# rev1.net
KiCad netlist of a schematic drawn in Altium Designer
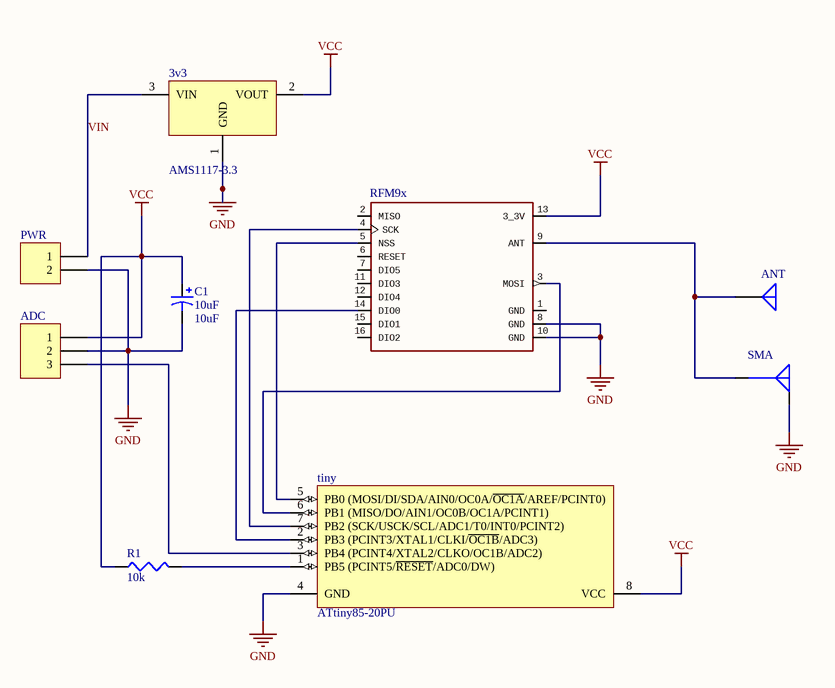
[diagram p0: rev1.SchDoc]

(export (version "E")
  (design (tool "Eeschema 10.0.6"))
  (components
    (comp (ref "3v3")
      (value "AMS1117-3.3")
      (footprint "SOT-223")
      (description "3.3V  3-Terminal Adjustable Positive Voltage Regulator")
      (libsource (lib "Analog IC") (part "AMS1117-3.3"))
    )
    (comp (ref "ADC")
      (value "~")
      (footprint "HDR1X3")
      (description "Header, 3-Pin")
      (fields (field (name "PUBLISHER") "Altium Limited"))
      (libsource (lib "Miscellaneous Connectors") (part "Header 3"))
    )
    (comp (ref "ANT")
      (value "~")
      (footprint "PIN1")
      (description "Generic Antenna")
      (fields (field (name "PUBLISHER") "Altium Limited"))
      (libsource (lib "Miscellaneous Devices") (part "Antenna"))
    )
    (comp (ref "C1")
      (value "10uF")
      (footprint "C0805")
      (description "Polarized Capacitor (Surface Mount)")
      (fields (field (name "ALTIUM_VALUE") "10uF") (field (name "PUBLISHER") "Altium Limited"))
      (libsource (lib "LoRa_v1") (part "Cap Pol3"))
    )
    (comp (ref "PWR")
      (value "~")
      (footprint "HDR1X2")
      (description "Header, 2-Pin")
      (fields (field (name "PUBLISHER") "Altium Limited"))
      (libsource (lib "Miscellaneous Connectors") (part "Header 2"))
    )
    (comp (ref "R1")
      (value "10k")
      (footprint "C0805")
      (description "Resistor")
      (fields (field (name "PUBLISHER") "Altium Limited"))
      (libsource (lib "LoRa_v1") (part "Res3"))
    )
    (comp (ref "RFM9x")
      (value "~")
      (footprint "XCVR_RFM95W-868S2")
      (fields (field (name "MF") "RF") (field (name "MP") "RFM95W-868S2"))
      (libsource (lib "RFM95W-868S2") (part "RFM95W-868S2"))
    )
    (comp (ref "SMA")
      (value "~")
      (footprint "LINX CONREVSMA003.062")
      (libsource (lib "RF Connector") (part "RF Connector - SMA"))
    )
    (comp (ref "tiny")
      (value "ATtiny85-20PU")
      (footprint "8P3")
      (libsource (lib "Atmel Microcontroller tinyAVR") (part "ATtiny85-20PU"))
    )
  )
  (nets
    (net (code "1") (name "/VIN") (class "Default")
      (node (ref "3v3") (pin "3") (pinfunction "VIN_3") (pintype "passive"))
      (node (ref "PWR") (pin "1") (pinfunction "1_1") (pintype "passive"))
    )
    (net (code "2") (name "GND") (class "Default")
      (node (ref "3v3") (pin "1") (pinfunction "GND_1") (pintype "passive"))
      (node (ref "ADC") (pin "2") (pinfunction "2_2") (pintype "passive"))
      (node (ref "C1") (pin "2") (pinfunction "2_2") (pintype "passive"))
      (node (ref "PWR") (pin "2") (pinfunction "2_2") (pintype "passive"))
      (node (ref "RFM9x") (pin "10") (pinfunction "GND_10") (pintype "power_in"))
      (node (ref "RFM9x") (pin "8") (pinfunction "GND_8") (pintype "power_in"))
      (node (ref "SMA") (pin "G") (pinfunction "G_G") (pintype "passive"))
      (node (ref "tiny") (pin "4") (pinfunction "GND_4") (pintype "power_in"))
    )
    (net (code "3") (name "Net-(ANT-A)") (class "Default")
      (node (ref "ANT") (pin "1") (pinfunction "A_1") (pintype "passive"))
      (node (ref "RFM9x") (pin "9") (pinfunction "ANT_9") (pintype "passive"))
      (node (ref "SMA") (pin "S") (pinfunction "S_S") (pintype "passive"))
    )
    (net (code "4") (name "Net-(RFM9x-DIO0)") (class "Default")
      (node (ref "RFM9x") (pin "14") (pinfunction "DIO0_14") (pintype "passive"))
      (node (ref "tiny") (pin "2") (pinfunction "PB3_(PCINT3/XTAL1/CLKI/~{OC1B}/ADC3)_2") (pintype "bidirectional"))
    )
    (net (code "5") (name "Net-(RFM9x-MOSI)") (class "Default")
      (node (ref "RFM9x") (pin "3") (pinfunction "MOSI_3") (pintype "output"))
      (node (ref "tiny") (pin "6") (pinfunction "PB1_(MISO/DO/AIN1/OC0B/OC1A/PCINT1)_6") (pintype "bidirectional"))
    )
    (net (code "6") (name "Net-(RFM9x-NSS)") (class "Default")
      (node (ref "RFM9x") (pin "5") (pinfunction "NSS_5") (pintype "passive"))
      (node (ref "tiny") (pin "5") (pinfunction "PB0_(MOSI/DI/SDA/AIN0/OC0A/~{OC1A}/AREF/PCINT0)_5") (pintype "bidirectional"))
    )
    (net (code "7") (name "Net-(RFM9x-SCK)") (class "Default")
      (node (ref "RFM9x") (pin "4") (pinfunction "SCK_4") (pintype "passive"))
      (node (ref "tiny") (pin "7") (pinfunction "PB2_(SCK/USCK/SCL/ADC1/T0/INT0/PCINT2)_7") (pintype "bidirectional"))
    )
    (net (code "8") (name "Net-(tiny-PB4_(PCINT4{slash}XTAL2{slash}CLKO{slash}OC1B{slash}ADC2))") (class "Default")
      (node (ref "ADC") (pin "3") (pinfunction "3_3") (pintype "passive"))
      (node (ref "tiny") (pin "3") (pinfunction "PB4_(PCINT4/XTAL2/CLKO/OC1B/ADC2)_3") (pintype "bidirectional"))
    )
    (net (code "9") (name "Net-(tiny-PB5_(PCINT5{slash}~{RESET}{slash}ADC0{slash}DW))") (class "Default")
      (node (ref "R1") (pin "2") (pinfunction "2_2") (pintype "passive"))
      (node (ref "tiny") (pin "1") (pinfunction "PB5_(PCINT5/~{RESET}/ADC0/DW)_1") (pintype "bidirectional"))
    )
    (net (code "10") (name "VCC") (class "Default")
      (node (ref "3v3") (pin "2") (pinfunction "VOUT_2") (pintype "passive"))
      (node (ref "ADC") (pin "1") (pinfunction "1_1") (pintype "passive"))
      (node (ref "C1") (pin "1") (pinfunction "1_1") (pintype "passive"))
      (node (ref "R1") (pin "1") (pinfunction "1_1") (pintype "passive"))
      (node (ref "RFM9x") (pin "13") (pinfunction "3_3V_13") (pintype "power_in"))
      (node (ref "tiny") (pin "8") (pinfunction "VCC_8") (pintype "power_in"))
    )
    (net (code "11") (name "unconnected-(RFM9x-DIO1-Pad15)") (class "Default")
      (node (ref "RFM9x") (pin "15") (pinfunction "DIO1_15") (pintype "passive"))
    )
    (net (code "12") (name "unconnected-(RFM9x-DIO2-Pad16)") (class "Default")
      (node (ref "RFM9x") (pin "16") (pinfunction "DIO2_16") (pintype "passive"))
    )
    (net (code "13") (name "unconnected-(RFM9x-DIO3-Pad11)") (class "Default")
      (node (ref "RFM9x") (pin "11") (pinfunction "DIO3_11") (pintype "passive"))
    )
    (net (code "14") (name "unconnected-(RFM9x-DIO4-Pad12)") (class "Default")
      (node (ref "RFM9x") (pin "12") (pinfunction "DIO4_12") (pintype "passive"))
    )
    (net (code "15") (name "unconnected-(RFM9x-DIO5-Pad7)") (class "Default")
      (node (ref "RFM9x") (pin "7") (pinfunction "DIO5_7") (pintype "passive"))
    )
    (net (code "16") (name "unconnected-(RFM9x-GND-Pad1)") (class "Default")
      (node (ref "RFM9x") (pin "1") (pinfunction "GND_1") (pintype "power_in"))
    )
    (net (code "17") (name "unconnected-(RFM9x-MISO-Pad2)") (class "Default")
      (node (ref "RFM9x") (pin "2") (pinfunction "MISO_2") (pintype "passive"))
    )
    (net (code "18") (name "unconnected-(RFM9x-RESET-Pad6)") (class "Default")
      (node (ref "RFM9x") (pin "6") (pinfunction "RESET_6") (pintype "passive"))
    )
  )
)
